# Sheet1.net
KiCad netlist of a schematic drawn in Altium Designer
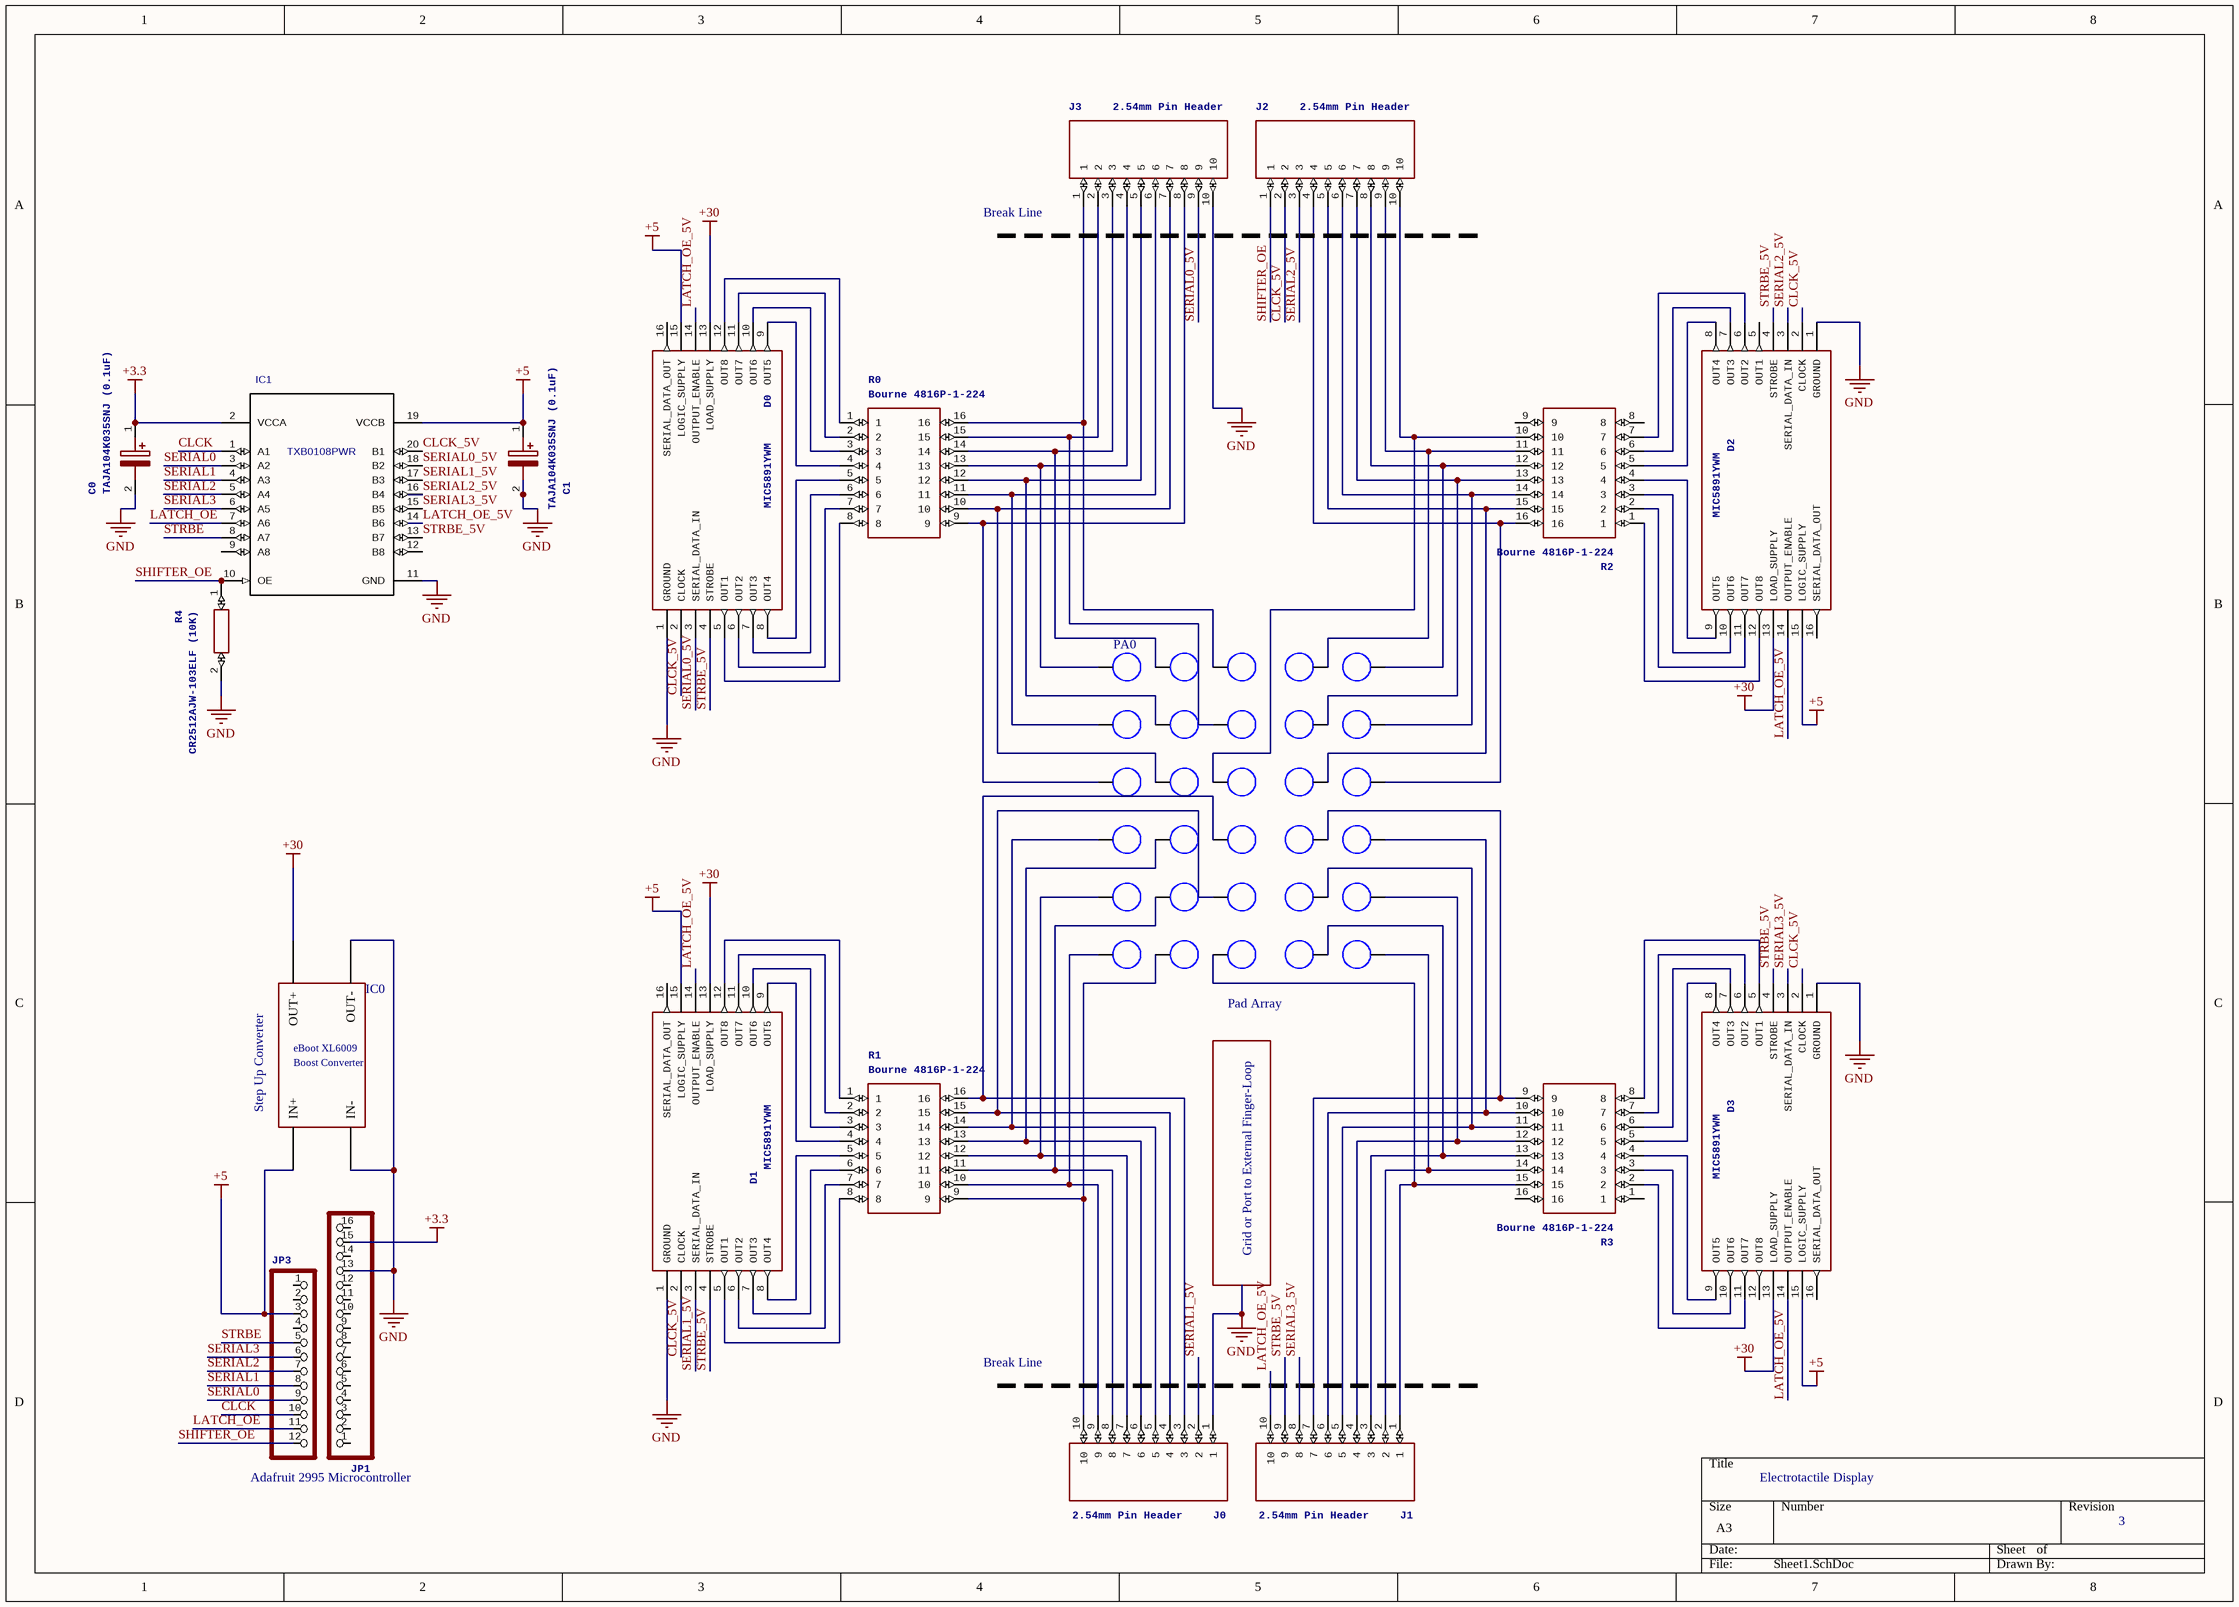
[diagram p0: Sheet1.SchDoc]

(export (version "E")
  (design (tool "Eeschema 10.0.6"))
  (components
    (comp (ref "C0")
      (value "TAJA104K035SNJ (0.1uF)")
      (footprint "CAPPM3216X180N")
      (fields
        (field (name "MOUSER_PART_NUMBER") "581-TAJA104K035SNJ")
        (field (name "MANUFACTURER_PART_NUMBER") "TAJA104K035SNJ")
      )
      (libsource (lib "TAJA104K035SNJ") (part "TAJA104K035SNJ"))
    )
    (comp (ref "C1")
      (value "TAJA104K035SNJ (0.1uF)")
      (footprint "CAPPM3216X180N")
      (fields
        (field (name "MOUSER_PART_NUMBER") "581-TAJA104K035SNJ")
        (field (name "MANUFACTURER_PART_NUMBER") "TAJA104K035SNJ")
      )
      (libsource (lib "TAJA104K035SNJ") (part "TAJA104K035SNJ"))
    )
    (comp (ref "D0")
      (value "MIC5891YWM")
      (footprint "SOIC127P1031X264-16N")
      (fields (field (name "MOUSER_PART_NUMBER") "998-MIC5891YWM"))
      (libsource (lib "MIC5891YWM") (part "MIC5891YWM"))
    )
    (comp (ref "D1")
      (value "MIC5891YWM")
      (footprint "SOIC127P1031X264-16N")
      (fields (field (name "MOUSER_PART_NUMBER") "998-MIC5891YWM"))
      (libsource (lib "MIC5891YWM") (part "MIC5891YWM"))
    )
    (comp (ref "D2")
      (value "MIC5891YWM")
      (footprint "SOIC127P1031X264-16N")
      (fields (field (name "MOUSER_PART_NUMBER") "998-MIC5891YWM"))
      (libsource (lib "MIC5891YWM") (part "MIC5891YWM"))
    )
    (comp (ref "D3")
      (value "MIC5891YWM")
      (footprint "SOIC127P1031X264-16N")
      (fields (field (name "MOUSER_PART_NUMBER") "998-MIC5891YWM"))
      (libsource (lib "MIC5891YWM") (part "MIC5891YWM"))
    )
    (comp (ref "IC0") (value "Step Up Converter") (libsource (lib "Boost") (part "Component_1")))
    (comp (ref "IC1")
      (value "TXB0108PWR")
      (footprint "PW0020A_N")
      (fields (field (name "MANUFACTURER") "Texas Instruments"))
      (libsource (lib "AltiumV15") (part "TXB0108PWR"))
    )
    (comp (ref "J0")
      (value "2.54mm Pin Header")
      (footprint "HDRV10W64P0X254_1X10_2540X254X")
      (fields
        (field (name "MOUSER_PART_NUMBER") "710-61301011121")
        (field (name "MANUFACTURER_PART_NUMBER") "61301011121")
      )
      (libsource (lib "61301011121") (part "61301011121"))
    )
    (comp (ref "J1")
      (value "2.54mm Pin Header")
      (footprint "HDRV10W64P0X254_1X10_2540X254X")
      (fields
        (field (name "MOUSER_PART_NUMBER") "710-61301011121")
        (field (name "MANUFACTURER_PART_NUMBER") "61301011121")
      )
      (libsource (lib "61301011121") (part "61301011121"))
    )
    (comp (ref "J2")
      (value "2.54mm Pin Header")
      (footprint "HDRV10W64P0X254_1X10_2540X254X")
      (fields
        (field (name "MOUSER_PART_NUMBER") "710-61301011121")
        (field (name "MANUFACTURER_PART_NUMBER") "61301011121")
      )
      (libsource (lib "61301011121") (part "61301011121"))
    )
    (comp (ref "J3")
      (value "2.54mm Pin Header")
      (footprint "HDRV10W64P0X254_1X10_2540X254X")
      (fields
        (field (name "MOUSER_PART_NUMBER") "710-61301011121")
        (field (name "MANUFACTURER_PART_NUMBER") "61301011121")
      )
      (libsource (lib "61301011121") (part "61301011121"))
    )
    (comp (ref "JP1")
      (value "HEADER-1X16ROUND")
      (footprint "1X16_ROUND")
      (description "PIN HEADER")
      (libsource (lib "microbuilder") (part "HEADER-1X16ROUND"))
    )
    (comp (ref "JP3")
      (value "HEADER-1X12")
      (footprint "1X12_ROUND")
      (libsource (lib "microbuilder") (part "HEADER-1X12"))
    )
    (comp (ref "PA0") (value "Pad Array") (libsource (lib "pads") (part "Component_1")))
    (comp (ref "R0")
      (value "Bourne 4816P-1-224")
      (footprint "SOIC127P762X215-16N")
      (fields
        (field (name "MOUSER_PART_NUMBER") "652-4816P-1LF-22K")
        (field (name "MANUFACTURER_PART_NUMBER") "4816P-1-223LF")
      )
      (libsource (lib "4816P-1-223LF") (part "4816P-1-223LF"))
    )
    (comp (ref "R1")
      (value "Bourne 4816P-1-224")
      (footprint "SOIC127P762X215-16N")
      (fields
        (field (name "MOUSER_PART_NUMBER") "652-4816P-1LF-22K")
        (field (name "MANUFACTURER_PART_NUMBER") "4816P-1-223LF")
      )
      (libsource (lib "4816P-1-223LF") (part "4816P-1-223LF"))
    )
    (comp (ref "R2")
      (value "Bourne 4816P-1-224")
      (footprint "SOIC127P762X215-16N")
      (fields
        (field (name "MOUSER_PART_NUMBER") "652-4816P-1LF-22K")
        (field (name "MANUFACTURER_PART_NUMBER") "4816P-1-223LF")
      )
      (libsource (lib "4816P-1-223LF") (part "4816P-1-223LF"))
    )
    (comp (ref "R3")
      (value "Bourne 4816P-1-224")
      (footprint "SOIC127P762X215-16N")
      (fields
        (field (name "MOUSER_PART_NUMBER") "652-4816P-1LF-22K")
        (field (name "MANUFACTURER_PART_NUMBER") "4816P-1-223LF")
      )
      (libsource (lib "4816P-1-223LF") (part "4816P-1-223LF"))
    )
    (comp (ref "R4")
      (value "CR2512AJW-103ELF (10K)")
      (footprint "RESC6332X70N")
      (fields
        (field (name "MOUSER_PART_NUMBER") "652-CR2512AJW-103ELF")
        (field (name "MANUFACTURER_PART_NUMBER") "CR2512AJW-103ELF")
      )
      (libsource (lib "CR2512AJW-103ELF") (part "CR2512AJW-103ELF"))
    )
  )
  (nets
    (net (code "1") (name "+3.3") (class "Default")
      (node (ref "C0") (pin "1") (pinfunction "+_1") (pintype "bidirectional"))
      (node (ref "IC1") (pin "2") (pinfunction "VCCA_2") (pintype "power_in"))
      (node (ref "JP1") (pin "15") (pinfunction "15_15") (pintype "passive"))
    )
    (net (code "2") (name "+5") (class "Default")
      (node (ref "C1") (pin "1") (pinfunction "+_1") (pintype "bidirectional"))
      (node (ref "D0") (pin "15") (pinfunction "LOGIC_SUPPLY_15") (pintype "power_in"))
      (node (ref "D1") (pin "15") (pinfunction "LOGIC_SUPPLY_15") (pintype "power_in"))
      (node (ref "D2") (pin "15") (pinfunction "LOGIC_SUPPLY_15") (pintype "power_in"))
      (node (ref "D3") (pin "15") (pinfunction "LOGIC_SUPPLY_15") (pintype "power_in"))
      (node (ref "IC0") (pin "2") (pinfunction "IN+_2") (pintype "passive"))
      (node (ref "IC1") (pin "19") (pinfunction "VCCB_19") (pintype "power_in"))
      (node (ref "JP3") (pin "3") (pinfunction "3_3") (pintype "passive"))
    )
    (net (code "3") (name "+30") (class "Default")
      (node (ref "D0") (pin "13") (pinfunction "LOAD_SUPPLY_13") (pintype "power_in"))
      (node (ref "D1") (pin "13") (pinfunction "LOAD_SUPPLY_13") (pintype "power_in"))
      (node (ref "D2") (pin "13") (pinfunction "LOAD_SUPPLY_13") (pintype "power_in"))
      (node (ref "D3") (pin "13") (pinfunction "LOAD_SUPPLY_13") (pintype "power_in"))
      (node (ref "IC0") (pin "0") (pinfunction "OUT+_0") (pintype "passive"))
    )
    (net (code "4") (name "/CLCK") (class "Default")
      (node (ref "IC1") (pin "1") (pinfunction "A1_1") (pintype "bidirectional"))
      (node (ref "JP3") (pin "10") (pinfunction "10_10") (pintype "passive"))
    )
    (net (code "5") (name "/CLCK_5V") (class "Default")
      (node (ref "D0") (pin "2") (pinfunction "CLOCK_2") (pintype "passive"))
      (node (ref "D1") (pin "2") (pinfunction "CLOCK_2") (pintype "passive"))
      (node (ref "D2") (pin "2") (pinfunction "CLOCK_2") (pintype "passive"))
      (node (ref "D3") (pin "2") (pinfunction "CLOCK_2") (pintype "passive"))
      (node (ref "IC1") (pin "20") (pinfunction "B1_20") (pintype "bidirectional"))
      (node (ref "J2") (pin "2") (pinfunction "2_2") (pintype "bidirectional"))
    )
    (net (code "6") (name "/LATCH_OE") (class "Default")
      (node (ref "IC1") (pin "7") (pinfunction "A6_7") (pintype "bidirectional"))
      (node (ref "JP3") (pin "11") (pinfunction "11_11") (pintype "passive"))
    )
    (net (code "7") (name "/LATCH_OE_5V") (class "Default")
      (node (ref "D0") (pin "14") (pinfunction "OUTPUT_ENABLE_14") (pintype "passive"))
      (node (ref "D1") (pin "14") (pinfunction "OUTPUT_ENABLE_14") (pintype "passive"))
      (node (ref "D2") (pin "14") (pinfunction "OUTPUT_ENABLE_14") (pintype "passive"))
      (node (ref "D3") (pin "14") (pinfunction "OUTPUT_ENABLE_14") (pintype "passive"))
      (node (ref "IC1") (pin "14") (pinfunction "B6_14") (pintype "bidirectional"))
      (node (ref "J1") (pin "10") (pinfunction "10_10") (pintype "bidirectional"))
    )
    (net (code "8") (name "/SERIAL0") (class "Default")
      (node (ref "IC1") (pin "3") (pinfunction "A2_3") (pintype "bidirectional"))
      (node (ref "JP3") (pin "9") (pinfunction "9_9") (pintype "passive"))
    )
    (net (code "9") (name "/SERIAL0_5V") (class "Default")
      (node (ref "D0") (pin "3") (pinfunction "SERIAL_DATA_IN_3") (pintype "passive"))
      (node (ref "IC1") (pin "18") (pinfunction "B2_18") (pintype "bidirectional"))
      (node (ref "J3") (pin "9") (pinfunction "9_9") (pintype "bidirectional"))
    )
    (net (code "10") (name "/SERIAL1") (class "Default")
      (node (ref "IC1") (pin "4") (pinfunction "A3_4") (pintype "bidirectional"))
      (node (ref "JP3") (pin "8") (pinfunction "8_8") (pintype "passive"))
    )
    (net (code "11") (name "/SERIAL1_5V") (class "Default")
      (node (ref "D1") (pin "3") (pinfunction "SERIAL_DATA_IN_3") (pintype "passive"))
      (node (ref "IC1") (pin "17") (pinfunction "B3_17") (pintype "bidirectional"))
      (node (ref "J0") (pin "2") (pinfunction "2_2") (pintype "bidirectional"))
    )
    (net (code "12") (name "/SERIAL2") (class "Default")
      (node (ref "IC1") (pin "5") (pinfunction "A4_5") (pintype "bidirectional"))
      (node (ref "JP3") (pin "7") (pinfunction "7_7") (pintype "passive"))
    )
    (net (code "13") (name "/SERIAL2_5V") (class "Default")
      (node (ref "D2") (pin "3") (pinfunction "SERIAL_DATA_IN_3") (pintype "passive"))
      (node (ref "IC1") (pin "16") (pinfunction "B4_16") (pintype "bidirectional"))
      (node (ref "J2") (pin "3") (pinfunction "3_3") (pintype "bidirectional"))
    )
    (net (code "14") (name "/SERIAL3") (class "Default")
      (node (ref "IC1") (pin "6") (pinfunction "A5_6") (pintype "bidirectional"))
      (node (ref "JP3") (pin "6") (pinfunction "6_6") (pintype "passive"))
    )
    (net (code "15") (name "/SERIAL3_5V") (class "Default")
      (node (ref "D3") (pin "3") (pinfunction "SERIAL_DATA_IN_3") (pintype "passive"))
      (node (ref "IC1") (pin "15") (pinfunction "B5_15") (pintype "bidirectional"))
      (node (ref "J1") (pin "8") (pinfunction "8_8") (pintype "bidirectional"))
    )
    (net (code "16") (name "/SHIFTER_OE") (class "Default")
      (node (ref "IC1") (pin "10") (pinfunction "OE_10") (pintype "input"))
      (node (ref "J2") (pin "1") (pinfunction "1_1") (pintype "bidirectional"))
      (node (ref "JP3") (pin "12") (pinfunction "12_12") (pintype "passive"))
      (node (ref "R4") (pin "1") (pinfunction "1_1") (pintype "bidirectional"))
    )
    (net (code "17") (name "/STRBE") (class "Default")
      (node (ref "IC1") (pin "8") (pinfunction "A7_8") (pintype "bidirectional"))
      (node (ref "JP3") (pin "5") (pinfunction "5_5") (pintype "passive"))
    )
    (net (code "18") (name "/STRBE_5V") (class "Default")
      (node (ref "D0") (pin "4") (pinfunction "STROBE_4") (pintype "passive"))
      (node (ref "D1") (pin "4") (pinfunction "STROBE_4") (pintype "passive"))
      (node (ref "D2") (pin "4") (pinfunction "STROBE_4") (pintype "passive"))
      (node (ref "D3") (pin "4") (pinfunction "STROBE_4") (pintype "passive"))
      (node (ref "IC1") (pin "13") (pinfunction "B7_13") (pintype "bidirectional"))
      (node (ref "J1") (pin "9") (pinfunction "9_9") (pintype "bidirectional"))
    )
    (net (code "19") (name "GND") (class "Default")
      (node (ref "C0") (pin "2") (pinfunction "-_2") (pintype "bidirectional"))
      (node (ref "C1") (pin "2") (pinfunction "-_2") (pintype "bidirectional"))
      (node (ref "D0") (pin "1") (pinfunction "GROUND_1") (pintype "power_in"))
      (node (ref "D1") (pin "1") (pinfunction "GROUND_1") (pintype "power_in"))
      (node (ref "D2") (pin "1") (pinfunction "GROUND_1") (pintype "power_in"))
      (node (ref "D3") (pin "1") (pinfunction "GROUND_1") (pintype "power_in"))
      (node (ref "IC0") (pin "1") (pinfunction "OUT-_1") (pintype "passive"))
      (node (ref "IC0") (pin "3") (pinfunction "IN-_3") (pintype "passive"))
      (node (ref "IC1") (pin "11") (pinfunction "GND_11") (pintype "power_in"))
      (node (ref "J0") (pin "1") (pinfunction "1_1") (pintype "bidirectional"))
      (node (ref "J3") (pin "10") (pinfunction "10_10") (pintype "bidirectional"))
      (node (ref "JP1") (pin "13") (pinfunction "13_13") (pintype "passive"))
      (node (ref "R4") (pin "2") (pinfunction "2_2") (pintype "bidirectional"))
    )
    (net (code "20") (name "Net-(D0-OUT1)") (class "Default")
      (node (ref "D0") (pin "5") (pinfunction "OUT1_5") (pintype "output"))
      (node (ref "R0") (pin "8") (pinfunction "8_8") (pintype "bidirectional"))
    )
    (net (code "21") (name "Net-(D0-OUT2)") (class "Default")
      (node (ref "D0") (pin "6") (pinfunction "OUT2_6") (pintype "output"))
      (node (ref "R0") (pin "7") (pinfunction "7_7") (pintype "bidirectional"))
    )
    (net (code "22") (name "Net-(D0-OUT3)") (class "Default")
      (node (ref "D0") (pin "7") (pinfunction "OUT3_7") (pintype "output"))
      (node (ref "R0") (pin "6") (pinfunction "6_6") (pintype "bidirectional"))
    )
    (net (code "23") (name "Net-(D0-OUT4)") (class "Default")
      (node (ref "D0") (pin "8") (pinfunction "OUT4_8") (pintype "output"))
      (node (ref "R0") (pin "5") (pinfunction "5_5") (pintype "bidirectional"))
    )
    (net (code "24") (name "Net-(D0-OUT5)") (class "Default")
      (node (ref "D0") (pin "9") (pinfunction "OUT5_9") (pintype "output"))
      (node (ref "R0") (pin "4") (pinfunction "4_4") (pintype "bidirectional"))
    )
    (net (code "25") (name "Net-(D0-OUT6)") (class "Default")
      (node (ref "D0") (pin "10") (pinfunction "OUT6_10") (pintype "output"))
      (node (ref "R0") (pin "3") (pinfunction "3_3") (pintype "bidirectional"))
    )
    (net (code "26") (name "Net-(D0-OUT7)") (class "Default")
      (node (ref "D0") (pin "11") (pinfunction "OUT7_11") (pintype "output"))
      (node (ref "R0") (pin "2") (pinfunction "2_2") (pintype "bidirectional"))
    )
    (net (code "27") (name "Net-(D0-OUT8)") (class "Default")
      (node (ref "D0") (pin "12") (pinfunction "OUT8_12") (pintype "output"))
      (node (ref "R0") (pin "1") (pinfunction "1_1") (pintype "bidirectional"))
    )
    (net (code "28") (name "Net-(D1-OUT1)") (class "Default")
      (node (ref "D1") (pin "5") (pinfunction "OUT1_5") (pintype "output"))
      (node (ref "R1") (pin "8") (pinfunction "8_8") (pintype "bidirectional"))
    )
    (net (code "29") (name "Net-(D1-OUT2)") (class "Default")
      (node (ref "D1") (pin "6") (pinfunction "OUT2_6") (pintype "output"))
      (node (ref "R1") (pin "7") (pinfunction "7_7") (pintype "bidirectional"))
    )
    (net (code "30") (name "Net-(D1-OUT3)") (class "Default")
      (node (ref "D1") (pin "7") (pinfunction "OUT3_7") (pintype "output"))
      (node (ref "R1") (pin "6") (pinfunction "6_6") (pintype "bidirectional"))
    )
    (net (code "31") (name "Net-(D1-OUT4)") (class "Default")
      (node (ref "D1") (pin "8") (pinfunction "OUT4_8") (pintype "output"))
      (node (ref "R1") (pin "5") (pinfunction "5_5") (pintype "bidirectional"))
    )
    (net (code "32") (name "Net-(D1-OUT5)") (class "Default")
      (node (ref "D1") (pin "9") (pinfunction "OUT5_9") (pintype "output"))
      (node (ref "R1") (pin "4") (pinfunction "4_4") (pintype "bidirectional"))
    )
    (net (code "33") (name "Net-(D1-OUT6)") (class "Default")
      (node (ref "D1") (pin "10") (pinfunction "OUT6_10") (pintype "output"))
      (node (ref "R1") (pin "3") (pinfunction "3_3") (pintype "bidirectional"))
    )
    (net (code "34") (name "Net-(D1-OUT7)") (class "Default")
      (node (ref "D1") (pin "11") (pinfunction "OUT7_11") (pintype "output"))
      (node (ref "R1") (pin "2") (pinfunction "2_2") (pintype "bidirectional"))
    )
    (net (code "35") (name "Net-(D1-OUT8)") (class "Default")
      (node (ref "D1") (pin "12") (pinfunction "OUT8_12") (pintype "output"))
      (node (ref "R1") (pin "1") (pinfunction "1_1") (pintype "bidirectional"))
    )
    (net (code "36") (name "Net-(D2-OUT2)") (class "Default")
      (node (ref "D2") (pin "6") (pinfunction "OUT2_6") (pintype "output"))
      (node (ref "R2") (pin "7") (pinfunction "7_7") (pintype "bidirectional"))
    )
    (net (code "37") (name "Net-(D2-OUT3)") (class "Default")
      (node (ref "D2") (pin "7") (pinfunction "OUT3_7") (pintype "output"))
      (node (ref "R2") (pin "6") (pinfunction "6_6") (pintype "bidirectional"))
    )
    (net (code "38") (name "Net-(D2-OUT4)") (class "Default")
      (node (ref "D2") (pin "8") (pinfunction "OUT4_8") (pintype "output"))
      (node (ref "R2") (pin "5") (pinfunction "5_5") (pintype "bidirectional"))
    )
    (net (code "39") (name "Net-(D2-OUT5)") (class "Default")
      (node (ref "D2") (pin "9") (pinfunction "OUT5_9") (pintype "output"))
      (node (ref "R2") (pin "4") (pinfunction "4_4") (pintype "bidirectional"))
    )
    (net (code "40") (name "Net-(D2-OUT6)") (class "Default")
      (node (ref "D2") (pin "10") (pinfunction "OUT6_10") (pintype "output"))
      (node (ref "R2") (pin "3") (pinfunction "3_3") (pintype "bidirectional"))
    )
    (net (code "41") (name "Net-(D2-OUT7)") (class "Default")
      (node (ref "D2") (pin "11") (pinfunction "OUT7_11") (pintype "output"))
      (node (ref "R2") (pin "2") (pinfunction "2_2") (pintype "bidirectional"))
    )
    (net (code "42") (name "Net-(D2-OUT8)") (class "Default")
      (node (ref "D2") (pin "12") (pinfunction "OUT8_12") (pintype "output"))
      (node (ref "R2") (pin "1") (pinfunction "1_1") (pintype "bidirectional"))
    )
    (net (code "43") (name "Net-(D3-OUT1)") (class "Default")
      (node (ref "D3") (pin "5") (pinfunction "OUT1_5") (pintype "output"))
      (node (ref "R3") (pin "8") (pinfunction "8_8") (pintype "bidirectional"))
    )
    (net (code "44") (name "Net-(D3-OUT2)") (class "Default")
      (node (ref "D3") (pin "6") (pinfunction "OUT2_6") (pintype "output"))
      (node (ref "R3") (pin "7") (pinfunction "7_7") (pintype "bidirectional"))
    )
    (net (code "45") (name "Net-(D3-OUT3)") (class "Default")
      (node (ref "D3") (pin "7") (pinfunction "OUT3_7") (pintype "output"))
      (node (ref "R3") (pin "6") (pinfunction "6_6") (pintype "bidirectional"))
    )
    (net (code "46") (name "Net-(D3-OUT4)") (class "Default")
      (node (ref "D3") (pin "8") (pinfunction "OUT4_8") (pintype "output"))
      (node (ref "R3") (pin "5") (pinfunction "5_5") (pintype "bidirectional"))
    )
    (net (code "47") (name "Net-(D3-OUT5)") (class "Default")
      (node (ref "D3") (pin "9") (pinfunction "OUT5_9") (pintype "output"))
      (node (ref "R3") (pin "4") (pinfunction "4_4") (pintype "bidirectional"))
    )
    (net (code "48") (name "Net-(D3-OUT6)") (class "Default")
      (node (ref "D3") (pin "10") (pinfunction "OUT6_10") (pintype "output"))
      (node (ref "R3") (pin "3") (pinfunction "3_3") (pintype "bidirectional"))
    )
    (net (code "49") (name "Net-(D3-OUT7)") (class "Default")
      (node (ref "D3") (pin "11") (pinfunction "OUT7_11") (pintype "output"))
      (node (ref "R3") (pin "2") (pinfunction "2_2") (pintype "bidirectional"))
    )
    (net (code "50") (name "Net-(PA0-0)") (class "Default")
      (node (ref "J1") (pin "2") (pinfunction "2_2") (pintype "bidirectional"))
      (node (ref "PA0") (pin "4") (pinfunction "0_4") (pintype "passive"))
      (node (ref "R3") (pin "14") (pinfunction "14_14") (pintype "bidirectional"))
    )
    (net (code "51") (name "Net-(PA0-0)_1") (class "Default")
      (node (ref "J3") (pin "3") (pinfunction "3_3") (pintype "bidirectional"))
      (node (ref "PA0") (pin "4") (pinfunction "0_4") (pintype "passive"))
      (node (ref "R0") (pin "14") (pinfunction "14_14") (pintype "bidirectional"))
    )
    (net (code "52") (name "Net-(PA0-0)_2") (class "Default")
      (node (ref "J3") (pin "4") (pinfunction "4_4") (pintype "bidirectional"))
      (node (ref "PA0") (pin "4") (pinfunction "0_4") (pintype "passive"))
      (node (ref "R0") (pin "13") (pinfunction "13_13") (pintype "bidirectional"))
    )
    (net (code "53") (name "Net-(PA0-0)_3") (class "Default")
      (node (ref "J3") (pin "8") (pinfunction "8_8") (pintype "bidirectional"))
      (node (ref "PA0") (pin "4") (pinfunction "0_4") (pintype "passive"))
      (node (ref "R0") (pin "9") (pinfunction "9_9") (pintype "bidirectional"))
    )
    (net (code "54") (name "Net-(PA0-0)_4") (class "Default")
      (node (ref "J3") (pin "7") (pinfunction "7_7") (pintype "bidirectional"))
      (node (ref "PA0") (pin "4") (pinfunction "0_4") (pintype "passive"))
      (node (ref "R0") (pin "10") (pinfunction "10_10") (pintype "bidirectional"))
    )
    (net (code "55") (name "Net-(PA0-0)_5") (class "Default")
      (node (ref "J3") (pin "6") (pinfunction "6_6") (pintype "bidirectional"))
      (node (ref "PA0") (pin "4") (pinfunction "0_4") (pintype "passive"))
      (node (ref "R0") (pin "11") (pinfunction "11_11") (pintype "bidirectional"))
    )
    (net (code "56") (name "Net-(PA0-0)_6") (class "Default")
      (node (ref "J3") (pin "5") (pinfunction "5_5") (pintype "bidirectional"))
      (node (ref "PA0") (pin "4") (pinfunction "0_4") (pintype "passive"))
      (node (ref "R0") (pin "12") (pinfunction "12_12") (pintype "bidirectional"))
    )
    (net (code "57") (name "Net-(PA0-0)_7") (class "Default")
      (node (ref "J3") (pin "2") (pinfunction "2_2") (pintype "bidirectional"))
      (node (ref "PA0") (pin "4") (pinfunction "0_4") (pintype "passive"))
      (node (ref "R0") (pin "15") (pinfunction "15_15") (pintype "bidirectional"))
    )
    (net (code "58") (name "Net-(PA0-0)_8") (class "Default")
      (node (ref "J3") (pin "1") (pinfunction "1_1") (pintype "bidirectional"))
      (node (ref "PA0") (pin "4") (pinfunction "0_4") (pintype "passive"))
      (node (ref "R0") (pin "16") (pinfunction "16_16") (pintype "bidirectional"))
    )
    (net (code "59") (name "Net-(PA0-0)_9") (class "Default")
      (node (ref "J2") (pin "4") (pinfunction "4_4") (pintype "bidirectional"))
      (node (ref "PA0") (pin "4") (pinfunction "0_4") (pintype "passive"))
      (node (ref "R2") (pin "16") (pinfunction "16_16") (pintype "bidirectional"))
    )
    (net (code "60") (name "Net-(PA0-0)_10") (class "Default")
      (node (ref "J2") (pin "5") (pinfunction "5_5") (pintype "bidirectional"))
      (node (ref "PA0") (pin "4") (pinfunction "0_4") (pintype "passive"))
      (node (ref "R2") (pin "15") (pinfunction "15_15") (pintype "bidirectional"))
    )
    (net (code "61") (name "Net-(PA0-0)_11") (class "Default")
      (node (ref "J2") (pin "6") (pinfunction "6_6") (pintype "bidirectional"))
      (node (ref "PA0") (pin "4") (pinfunction "0_4") (pintype "passive"))
      (node (ref "R2") (pin "14") (pinfunction "14_14") (pintype "bidirectional"))
    )
    (net (code "62") (name "Net-(PA0-0)_12") (class "Default")
      (node (ref "J2") (pin "7") (pinfunction "7_7") (pintype "bidirectional"))
      (node (ref "PA0") (pin "4") (pinfunction "0_4") (pintype "passive"))
      (node (ref "R2") (pin "13") (pinfunction "13_13") (pintype "bidirectional"))
    )
    (net (code "63") (name "Net-(PA0-0)_13") (class "Default")
      (node (ref "J2") (pin "8") (pinfunction "8_8") (pintype "bidirectional"))
      (node (ref "PA0") (pin "4") (pinfunction "0_4") (pintype "passive"))
      (node (ref "R2") (pin "12") (pinfunction "12_12") (pintype "bidirectional"))
    )
    (net (code "64") (name "Net-(PA0-0)_14") (class "Default")
      (node (ref "J2") (pin "9") (pinfunction "9_9") (pintype "bidirectional"))
      (node (ref "PA0") (pin "4") (pinfunction "0_4") (pintype "passive"))
      (node (ref "R2") (pin "11") (pinfunction "11_11") (pintype "bidirectional"))
    )
    (net (code "65") (name "Net-(PA0-0)_15") (class "Default")
      (node (ref "J2") (pin "10") (pinfunction "10_10") (pintype "bidirectional"))
      (node (ref "PA0") (pin "4") (pinfunction "0_4") (pintype "passive"))
      (node (ref "R2") (pin "10") (pinfunction "10_10") (pintype "bidirectional"))
    )
    (net (code "66") (name "Net-(PA0-0)_16") (class "Default")
      (node (ref "J0") (pin "3") (pinfunction "3_3") (pintype "bidirectional"))
      (node (ref "PA0") (pin "4") (pinfunction "0_4") (pintype "passive"))
      (node (ref "R1") (pin "16") (pinfunction "16_16") (pintype "bidirectional"))
    )
    (net (code "67") (name "Net-(PA0-0)_17") (class "Default")
      (node (ref "J1") (pin "1") (pinfunction "1_1") (pintype "bidirectional"))
      (node (ref "PA0") (pin "4") (pinfunction "0_4") (pintype "passive"))
      (node (ref "R3") (pin "15") (pinfunction "15_15") (pintype "bidirectional"))
    )
    (net (code "68") (name "Net-(PA0-0)_18") (class "Default")
      (node (ref "J1") (pin "5") (pinfunction "5_5") (pintype "bidirectional"))
      (node (ref "PA0") (pin "4") (pinfunction "0_4") (pintype "passive"))
      (node (ref "R3") (pin "11") (pinfunction "11_11") (pintype "bidirectional"))
    )
    (net (code "69") (name "Net-(PA0-0)_19") (class "Default")
      (node (ref "J1") (pin "3") (pinfunction "3_3") (pintype "bidirectional"))
      (node (ref "PA0") (pin "4") (pinfunction "0_4") (pintype "passive"))
      (node (ref "R3") (pin "13") (pinfunction "13_13") (pintype "bidirectional"))
    )
    (net (code "70") (name "Net-(PA0-0)_20") (class "Default")
      (node (ref "J1") (pin "7") (pinfunction "7_7") (pintype "bidirectional"))
      (node (ref "PA0") (pin "4") (pinfunction "0_4") (pintype "passive"))
      (node (ref "R3") (pin "9") (pinfunction "9_9") (pintype "bidirectional"))
    )
    (net (code "71") (name "Net-(PA0-0)_21") (class "Default")
      (node (ref "J0") (pin "5") (pinfunction "5_5") (pintype "bidirectional"))
      (node (ref "PA0") (pin "4") (pinfunction "0_4") (pintype "passive"))
      (node (ref "R1") (pin "14") (pinfunction "14_14") (pintype "bidirectional"))
    )
    (net (code "72") (name "Net-(PA0-0)_22") (class "Default")
      (node (ref "J0") (pin "7") (pinfunction "7_7") (pintype "bidirectional"))
      (node (ref "PA0") (pin "4") (pinfunction "0_4") (pintype "passive"))
      (node (ref "R1") (pin "12") (pinfunction "12_12") (pintype "bidirectional"))
    )
    (net (code "73") (name "Net-(PA0-0)_23") (class "Default")
      (node (ref "J0") (pin "9") (pinfunction "9_9") (pintype "bidirectional"))
      (node (ref "PA0") (pin "4") (pinfunction "0_4") (pintype "passive"))
      (node (ref "R1") (pin "10") (pinfunction "10_10") (pintype "bidirectional"))
    )
    (net (code "74") (name "Net-(PA0-0)_24") (class "Default")
      (node (ref "J0") (pin "6") (pinfunction "6_6") (pintype "bidirectional"))
      (node (ref "PA0") (pin "4") (pinfunction "0_4") (pintype "passive"))
      (node (ref "R1") (pin "13") (pinfunction "13_13") (pintype "bidirectional"))
    )
    (net (code "75") (name "Net-(PA0-0)_25") (class "Default")
      (node (ref "J0") (pin "8") (pinfunction "8_8") (pintype "bidirectional"))
      (node (ref "PA0") (pin "4") (pinfunction "0_4") (pintype "passive"))
      (node (ref "R1") (pin "11") (pinfunction "11_11") (pintype "bidirectional"))
    )
    (net (code "76") (name "Net-(PA0-0)_26") (class "Default")
      (node (ref "J0") (pin "10") (pinfunction "10_10") (pintype "bidirectional"))
      (node (ref "PA0") (pin "4") (pinfunction "0_4") (pintype "passive"))
      (node (ref "R1") (pin "9") (pinfunction "9_9") (pintype "bidirectional"))
    )
    (net (code "77") (name "Net-(PA0-0)_27") (class "Default")
      (node (ref "J0") (pin "4") (pinfunction "4_4") (pintype "bidirectional"))
      (node (ref "PA0") (pin "4") (pinfunction "0_4") (pintype "passive"))
      (node (ref "R1") (pin "15") (pinfunction "15_15") (pintype "bidirectional"))
    )
    (net (code "78") (name "Net-(PA0-0)_28") (class "Default")
      (node (ref "J1") (pin "6") (pinfunction "6_6") (pintype "bidirectional"))
      (node (ref "PA0") (pin "4") (pinfunction "0_4") (pintype "passive"))
      (node (ref "R3") (pin "10") (pinfunction "10_10") (pintype "bidirectional"))
    )
    (net (code "79") (name "Net-(PA0-0)_29") (class "Default")
      (node (ref "J1") (pin "4") (pinfunction "4_4") (pintype "bidirectional"))
      (node (ref "PA0") (pin "4") (pinfunction "0_4") (pintype "passive"))
      (node (ref "R3") (pin "12") (pinfunction "12_12") (pintype "bidirectional"))
    )
    (net (code "80") (name "unconnected-(D0-SERIAL_DATA_OUT-Pad16)") (class "Default")
      (node (ref "D0") (pin "16") (pinfunction "SERIAL_DATA_OUT_16") (pintype "output"))
    )
    (net (code "81") (name "unconnected-(D1-SERIAL_DATA_OUT-Pad16)") (class "Default")
      (node (ref "D1") (pin "16") (pinfunction "SERIAL_DATA_OUT_16") (pintype "output"))
    )
    (net (code "82") (name "unconnected-(D2-OUT1-Pad5)") (class "Default")
      (node (ref "D2") (pin "5") (pinfunction "OUT1_5") (pintype "output"))
    )
    (net (code "83") (name "unconnected-(D2-SERIAL_DATA_OUT-Pad16)") (class "Default")
      (node (ref "D2") (pin "16") (pinfunction "SERIAL_DATA_OUT_16") (pintype "output"))
    )
    (net (code "84") (name "unconnected-(D3-OUT8-Pad12)") (class "Default")
      (node (ref "D3") (pin "12") (pinfunction "OUT8_12") (pintype "output"))
    )
    (net (code "85") (name "unconnected-(D3-SERIAL_DATA_OUT-Pad16)") (class "Default")
      (node (ref "D3") (pin "16") (pinfunction "SERIAL_DATA_OUT_16") (pintype "output"))
    )
    (net (code "86") (name "unconnected-(IC1-A8-Pad9)") (class "Default")
      (node (ref "IC1") (pin "9") (pinfunction "A8_9") (pintype "bidirectional"))
    )
    (net (code "87") (name "unconnected-(IC1-B8-Pad12)") (class "Default")
      (node (ref "IC1") (pin "12") (pinfunction "B8_12") (pintype "bidirectional"))
    )
    (net (code "88") (name "unconnected-(JP1-Pad1)") (class "Default")
      (node (ref "JP1") (pin "1") (pinfunction "1_1") (pintype "passive"))
    )
    (net (code "89") (name "unconnected-(JP1-Pad2)") (class "Default")
      (node (ref "JP1") (pin "2") (pinfunction "2_2") (pintype "passive"))
    )
    (net (code "90") (name "unconnected-(JP1-Pad3)") (class "Default")
      (node (ref "JP1") (pin "3") (pinfunction "3_3") (pintype "passive"))
    )
    (net (code "91") (name "unconnected-(JP1-Pad4)") (class "Default")
      (node (ref "JP1") (pin "4") (pinfunction "4_4") (pintype "passive"))
    )
    (net (code "92") (name "unconnected-(JP1-Pad5)") (class "Default")
      (node (ref "JP1") (pin "5") (pinfunction "5_5") (pintype "passive"))
    )
    (net (code "93") (name "unconnected-(JP1-Pad6)") (class "Default")
      (node (ref "JP1") (pin "6") (pinfunction "6_6") (pintype "passive"))
    )
    (net (code "94") (name "unconnected-(JP1-Pad7)") (class "Default")
      (node (ref "JP1") (pin "7") (pinfunction "7_7") (pintype "passive"))
    )
    (net (code "95") (name "unconnected-(JP1-Pad8)") (class "Default")
      (node (ref "JP1") (pin "8") (pinfunction "8_8") (pintype "passive"))
    )
    (net (code "96") (name "unconnected-(JP1-Pad9)") (class "Default")
      (node (ref "JP1") (pin "9") (pinfunction "9_9") (pintype "passive"))
    )
    (net (code "97") (name "unconnected-(JP1-Pad10)") (class "Default")
      (node (ref "JP1") (pin "10") (pinfunction "10_10") (pintype "passive"))
    )
    (net (code "98") (name "unconnected-(JP1-Pad11)") (class "Default")
      (node (ref "JP1") (pin "11") (pinfunction "11_11") (pintype "passive"))
    )
    (net (code "99") (name "unconnected-(JP1-Pad12)") (class "Default")
      (node (ref "JP1") (pin "12") (pinfunction "12_12") (pintype "passive"))
    )
    (net (code "100") (name "unconnected-(JP1-Pad14)") (class "Default")
      (node (ref "JP1") (pin "14") (pinfunction "14_14") (pintype "passive"))
    )
    (net (code "101") (name "unconnected-(JP1-Pad16)") (class "Default")
      (node (ref "JP1") (pin "16") (pinfunction "16_16") (pintype "passive"))
    )
    (net (code "102") (name "unconnected-(JP3-Pad1)") (class "Default")
      (node (ref "JP3") (pin "1") (pinfunction "1_1") (pintype "passive"))
    )
    (net (code "103") (name "unconnected-(JP3-Pad2)") (class "Default")
      (node (ref "JP3") (pin "2") (pinfunction "2_2") (pintype "passive"))
    )
    (net (code "104") (name "unconnected-(JP3-Pad4)") (class "Default")
      (node (ref "JP3") (pin "4") (pinfunction "4_4") (pintype "passive"))
    )
    (net (code "105") (name "unconnected-(R2-Pad8)") (class "Default")
      (node (ref "R2") (pin "8") (pinfunction "8_8") (pintype "bidirectional"))
    )
    (net (code "106") (name "unconnected-(R2-Pad9)") (class "Default")
      (node (ref "R2") (pin "9") (pinfunction "9_9") (pintype "bidirectional"))
    )
    (net (code "107") (name "unconnected-(R3-Pad1)") (class "Default")
      (node (ref "R3") (pin "1") (pinfunction "1_1") (pintype "bidirectional"))
    )
    (net (code "108") (name "unconnected-(R3-Pad16)") (class "Default")
      (node (ref "R3") (pin "16") (pinfunction "16_16") (pintype "bidirectional"))
    )
  )
)
